# Connectors.net
KiCad netlist of a schematic drawn in Altium Designer
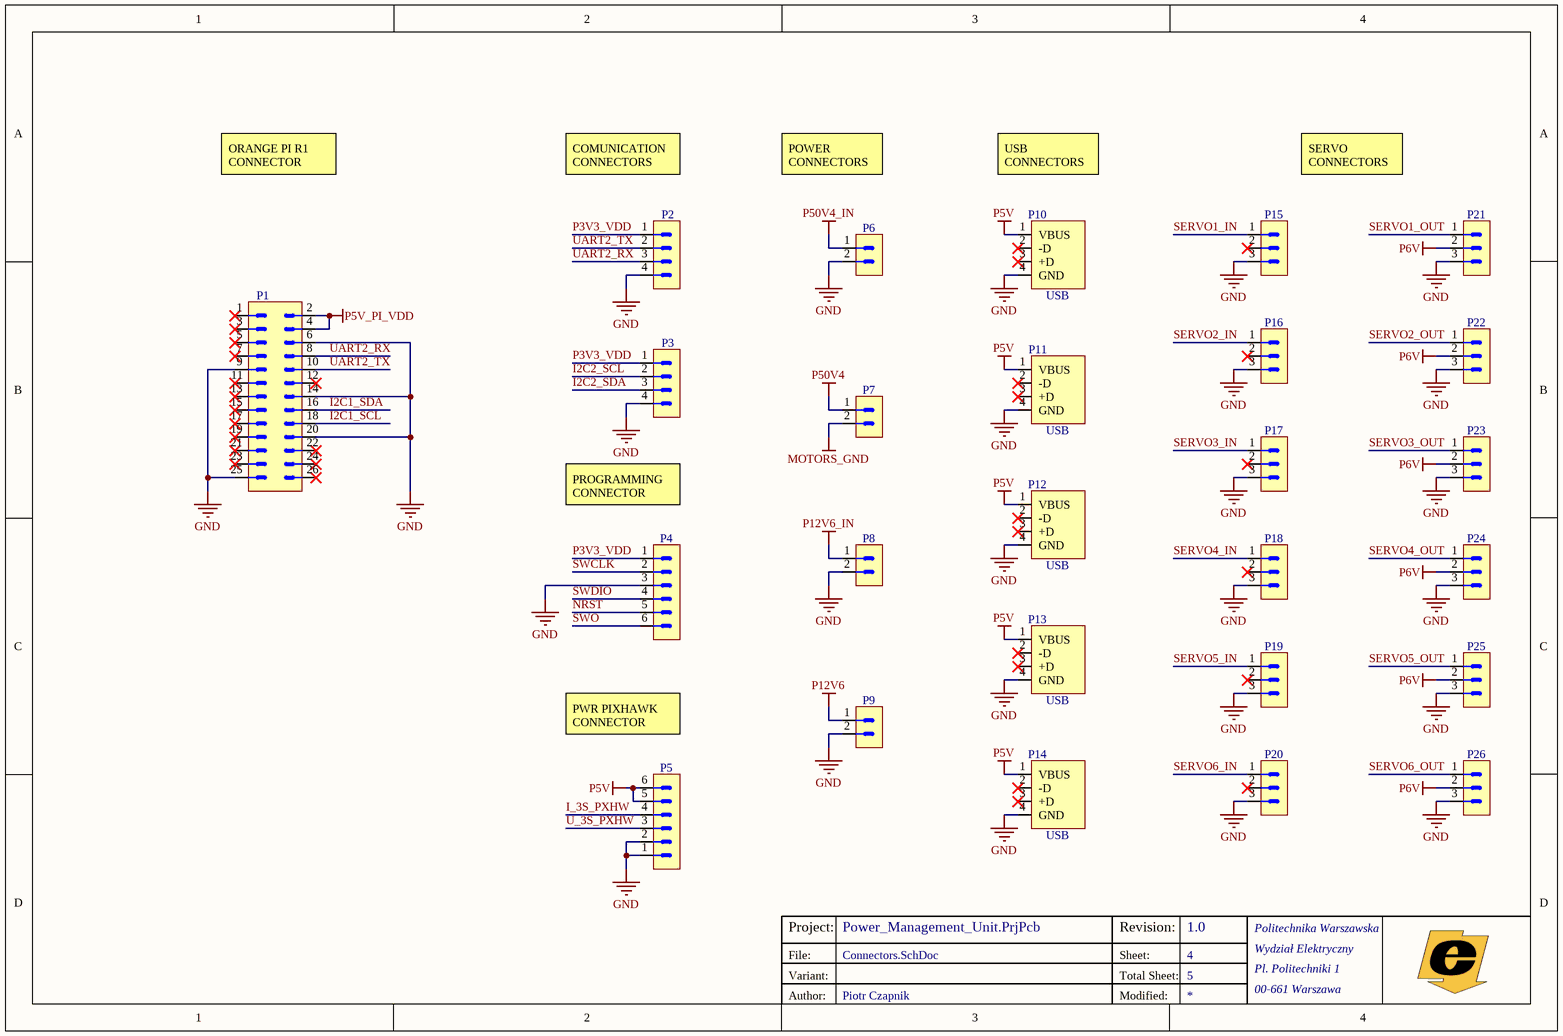
[diagram p0: Connectors.SchDoc]

(export (version "E")
  (design (tool "Eeschema 10.0.6"))
  (components
    (comp (ref "P1")
      (value "SAMTEC_SSW-113-02-G-D")
      (footprint "SAMTEC_SSW-113-02-G-D")
      (description "General Purpose Header: THT, 2.54mm, Female, Straight")
      (fields (field (name "MANUFACTURER") "GENERIC") (field (name "AUTHOR") "PC"))
      (libsource (lib "Connectors") (part "Header 13x2"))
    )
    (comp (ref "P2")
      (value "SAMTEC_TSW-104-07-G-S")
      (footprint "SAMTEC_TSW-104-07-G-S")
      (description "General Purpose Header: THT, 2.54mm, Male, Straight")
      (fields (field (name "MANUFACTURER") "GENERIC") (field (name "AUTHOR") "PC"))
      (libsource (lib "Connectors") (part "Header 4x1"))
    )
    (comp (ref "P3")
      (value "~")
      (footprint "BM04B-GHS-TBT")
      (description "JST GH series 4 pin vertical SMT connector, pitch 1.25mm, Right Angle")
      (fields
        (field (name "MANUFACTURER") "JST")
        (field (name "MANUFACTURER PART NUMBER") "BM04B-GHS-TBT (LF)(SN)")
        (field (name "AUTHOR") "PC")
      )
      (libsource (lib "Connectors") (part "Header 4x1"))
    )
    (comp (ref "P4")
      (value "MTLW-106-07-L-S-250")
      (footprint "SAMTEC_MTLW-106-07-L-S-250")
      (description "General Purpose Header: THT, 2.54mm, Male, Straight")
      (fields
        (field (name "MANUFACTURER") "GENERIC")
        (field (name "MANUFACTURER PART NUMBER") "HDR_THT_6X1V_M_2P54MM")
        (field (name "AUTHOR") "PC")
      )
      (libsource (lib "Connectors") (part "Header 6x1"))
    )
    (comp (ref "P5")
      (value "~")
      (footprint "BM06B-GHS-TBT")
      (description "JST GH series 6 pin vertical SMT connector, pitch 1.25mm, Right Angle")
      (fields
        (field (name "MANUFACTURER") "JST")
        (field (name "MANUFACTURER PART NUMBER") "BM06B-GHS-TBT (LF)(SN)")
        (field (name "AUTHOR") "PC")
      )
      (libsource (lib "") (part "Header 6x1_1"))
    )
    (comp (ref "P6")
      (value "XT60PW-M")
      (footprint "XT60PW-M")
      (description "XT60 male connector, right angle, 2 Positions, THT, 17.2x15.5mm body")
      (fields (field (name "MANUFACTURER") "GENERIC") (field (name "AUTHOR") "PC"))
      (libsource (lib "Connectors") (part "Header 2x1"))
    )
    (comp (ref "P7")
      (value "XT60PW-F")
      (footprint "XT60PW-F")
      (description "XT60 female connector, right angle, 2 Positions, THT, 17.2x15.5mm body")
      (fields (field (name "MANUFACTURER") "GENERIC") (field (name "AUTHOR") "PC"))
      (libsource (lib "Connectors") (part "Header 2x1"))
    )
    (comp (ref "P8")
      (value "XT60PW-M")
      (footprint "XT60PW-M")
      (description "XT60 male connector, right angle, 2 Positions, THT, 17.2x15.5mm body")
      (fields (field (name "MANUFACTURER") "GENERIC") (field (name "AUTHOR") "PC"))
      (libsource (lib "Connectors") (part "Header 2x1"))
    )
    (comp (ref "P9")
      (value "XT60PW-F")
      (footprint "XT60PW-F")
      (description "XT60 female connector, right angle, 2 Positions, THT, 17.2x15.5mm body")
      (fields (field (name "MANUFACTURER") "GENERIC") (field (name "AUTHOR") "PC"))
      (libsource (lib "Connectors") (part "Header 2x1"))
    )
    (comp (ref "P10")
      (value "USB")
      (footprint "USB-A-S-RA")
      (description "USB 2.0 Type A Female Connector 4-Pin THT")
      (fields
        (field (name "MANUFACTURER") "GENERIC")
        (field (name "MANUFACTURER PART NUMBER") "USB-A-S-RA")
        (field (name "AUTHOR") "BS")
      )
      (libsource (lib "Connectors") (part "Connector USB 4 Pin"))
    )
    (comp (ref "P11")
      (value "USB")
      (footprint "USB-A-S-RA")
      (description "USB 2.0 Type A Female Connector 4-Pin THT")
      (fields
        (field (name "MANUFACTURER") "GENERIC")
        (field (name "MANUFACTURER PART NUMBER") "USB-A-S-RA")
        (field (name "AUTHOR") "BS")
      )
      (libsource (lib "Connectors") (part "Connector USB 4 Pin"))
    )
    (comp (ref "P12")
      (value "USB")
      (footprint "USB-A-S-RA")
      (description "USB 2.0 Type A Female Connector 4-Pin THT")
      (fields
        (field (name "MANUFACTURER") "GENERIC")
        (field (name "MANUFACTURER PART NUMBER") "USB-A-S-RA")
        (field (name "AUTHOR") "BS")
      )
      (libsource (lib "Connectors") (part "Connector USB 4 Pin"))
    )
    (comp (ref "P13")
      (value "USB")
      (footprint "USB-A-S-RA")
      (description "USB 2.0 Type A Female Connector 4-Pin THT")
      (fields
        (field (name "MANUFACTURER") "GENERIC")
        (field (name "MANUFACTURER PART NUMBER") "USB-A-S-RA")
        (field (name "AUTHOR") "BS")
      )
      (libsource (lib "Connectors") (part "Connector USB 4 Pin"))
    )
    (comp (ref "P14")
      (value "USB")
      (footprint "USB-A-S-RA")
      (description "USB 2.0 Type A Female Connector 4-Pin THT")
      (fields
        (field (name "MANUFACTURER") "GENERIC")
        (field (name "MANUFACTURER PART NUMBER") "USB-A-S-RA")
        (field (name "AUTHOR") "BS")
      )
      (libsource (lib "Connectors") (part "Connector USB 4 Pin"))
    )
    (comp (ref "P15")
      (value "826926-3")
      (footprint "Header_3x1_2.54mm_M")
      (description "General Purpose Header: THT, 2.54mm, Male, Straight")
      (fields (field (name "MANUFACTURER") "GENERIC") (field (name "AUTHOR") "JK"))
      (libsource (lib "Connectors") (part "Header 3x1"))
    )
    (comp (ref "P16")
      (value "826926-3")
      (footprint "Header_3x1_2.54mm_M")
      (description "General Purpose Header: THT, 2.54mm, Male, Straight")
      (fields (field (name "MANUFACTURER") "GENERIC") (field (name "AUTHOR") "JK"))
      (libsource (lib "Connectors") (part "Header 3x1"))
    )
    (comp (ref "P17")
      (value "826926-3")
      (footprint "Header_3x1_2.54mm_M")
      (description "General Purpose Header: THT, 2.54mm, Male, Straight")
      (fields (field (name "MANUFACTURER") "GENERIC") (field (name "AUTHOR") "JK"))
      (libsource (lib "Connectors") (part "Header 3x1"))
    )
    (comp (ref "P18")
      (value "826926-3")
      (footprint "Header_3x1_2.54mm_M")
      (description "General Purpose Header: THT, 2.54mm, Male, Straight")
      (fields (field (name "MANUFACTURER") "GENERIC") (field (name "AUTHOR") "JK"))
      (libsource (lib "Connectors") (part "Header 3x1"))
    )
    (comp (ref "P19")
      (value "826926-3")
      (footprint "Header_3x1_2.54mm_M")
      (description "General Purpose Header: THT, 2.54mm, Male, Straight")
      (fields (field (name "MANUFACTURER") "GENERIC") (field (name "AUTHOR") "JK"))
      (libsource (lib "Connectors") (part "Header 3x1"))
    )
    (comp (ref "P20")
      (value "826926-3")
      (footprint "Header_3x1_2.54mm_M")
      (description "General Purpose Header: THT, 2.54mm, Male, Straight")
      (fields (field (name "MANUFACTURER") "GENERIC") (field (name "AUTHOR") "JK"))
      (libsource (lib "Connectors") (part "Header 3x1"))
    )
    (comp (ref "P21")
      (value "826926-3")
      (footprint "Header_3x1_2.54mm_M")
      (description "General Purpose Header: THT, 2.54mm, Male, Straight")
      (fields (field (name "MANUFACTURER") "GENERIC") (field (name "AUTHOR") "JK"))
      (libsource (lib "Connectors") (part "Header 3x1"))
    )
    (comp (ref "P22")
      (value "826926-3")
      (footprint "Header_3x1_2.54mm_M")
      (description "General Purpose Header: THT, 2.54mm, Male, Straight")
      (fields (field (name "MANUFACTURER") "GENERIC") (field (name "AUTHOR") "JK"))
      (libsource (lib "Connectors") (part "Header 3x1"))
    )
    (comp (ref "P23")
      (value "826926-3")
      (footprint "Header_3x1_2.54mm_M")
      (description "General Purpose Header: THT, 2.54mm, Male, Straight")
      (fields (field (name "MANUFACTURER") "GENERIC") (field (name "AUTHOR") "JK"))
      (libsource (lib "Connectors") (part "Header 3x1"))
    )
    (comp (ref "P24")
      (value "826926-3")
      (footprint "Header_3x1_2.54mm_M")
      (description "General Purpose Header: THT, 2.54mm, Male, Straight")
      (fields (field (name "MANUFACTURER") "GENERIC") (field (name "AUTHOR") "JK"))
      (libsource (lib "Connectors") (part "Header 3x1"))
    )
    (comp (ref "P25")
      (value "826926-3")
      (footprint "Header_3x1_2.54mm_M")
      (description "General Purpose Header: THT, 2.54mm, Male, Straight")
      (fields (field (name "MANUFACTURER") "GENERIC") (field (name "AUTHOR") "JK"))
      (libsource (lib "Connectors") (part "Header 3x1"))
    )
    (comp (ref "P26")
      (value "826926-3")
      (footprint "Header_3x1_2.54mm_M")
      (description "General Purpose Header: THT, 2.54mm, Male, Straight")
      (fields (field (name "MANUFACTURER") "GENERIC") (field (name "AUTHOR") "JK"))
      (libsource (lib "Connectors") (part "Header 3x1"))
    )
  )
  (nets
    (net (code "1") (name "/I2C1_SCL") (class "Default")
      (node (ref "P1") (pin "18") (pinfunction "18_18") (pintype "passive"))
    )
    (net (code "2") (name "/I2C1_SDA") (class "Default")
      (node (ref "P1") (pin "16") (pinfunction "16_16") (pintype "passive"))
    )
    (net (code "3") (name "/I2C2_SCL") (class "Default")
      (node (ref "P3") (pin "2") (pinfunction "2_2") (pintype "passive"))
    )
    (net (code "4") (name "/I2C2_SDA") (class "Default")
      (node (ref "P3") (pin "3") (pinfunction "3_3") (pintype "passive"))
    )
    (net (code "5") (name "/I_3S_PXHW") (class "Default")
      (node (ref "P5") (pin "4") (pinfunction "4_4") (pintype "passive"))
    )
    (net (code "6") (name "/NRST") (class "Default")
      (node (ref "P4") (pin "5") (pinfunction "5_5") (pintype "passive"))
    )
    (net (code "7") (name "/P3V3_VDD") (class "Default")
      (node (ref "P2") (pin "1") (pinfunction "1_1") (pintype "passive"))
      (node (ref "P3") (pin "1") (pinfunction "1_1") (pintype "passive"))
      (node (ref "P4") (pin "1") (pinfunction "1_1") (pintype "passive"))
    )
    (net (code "8") (name "/SERVO1_IN") (class "Default")
      (node (ref "P15") (pin "1") (pinfunction "1_1") (pintype "passive"))
    )
    (net (code "9") (name "/SERVO1_OUT") (class "Default")
      (node (ref "P21") (pin "1") (pinfunction "1_1") (pintype "passive"))
    )
    (net (code "10") (name "/SERVO2_IN") (class "Default")
      (node (ref "P16") (pin "1") (pinfunction "1_1") (pintype "passive"))
    )
    (net (code "11") (name "/SERVO2_OUT") (class "Default")
      (node (ref "P22") (pin "1") (pinfunction "1_1") (pintype "passive"))
    )
    (net (code "12") (name "/SERVO3_IN") (class "Default")
      (node (ref "P17") (pin "1") (pinfunction "1_1") (pintype "passive"))
    )
    (net (code "13") (name "/SERVO3_OUT") (class "Default")
      (node (ref "P23") (pin "1") (pinfunction "1_1") (pintype "passive"))
    )
    (net (code "14") (name "/SERVO4_IN") (class "Default")
      (node (ref "P18") (pin "1") (pinfunction "1_1") (pintype "passive"))
    )
    (net (code "15") (name "/SERVO4_OUT") (class "Default")
      (node (ref "P24") (pin "1") (pinfunction "1_1") (pintype "passive"))
    )
    (net (code "16") (name "/SERVO5_IN") (class "Default")
      (node (ref "P19") (pin "1") (pinfunction "1_1") (pintype "passive"))
    )
    (net (code "17") (name "/SERVO5_OUT") (class "Default")
      (node (ref "P25") (pin "1") (pinfunction "1_1") (pintype "passive"))
    )
    (net (code "18") (name "/SERVO6_IN") (class "Default")
      (node (ref "P20") (pin "1") (pinfunction "1_1") (pintype "passive"))
    )
    (net (code "19") (name "/SERVO6_OUT") (class "Default")
      (node (ref "P26") (pin "1") (pinfunction "1_1") (pintype "passive"))
    )
    (net (code "20") (name "/SWCLK") (class "Default")
      (node (ref "P4") (pin "2") (pinfunction "2_2") (pintype "passive"))
    )
    (net (code "21") (name "/SWDIO") (class "Default")
      (node (ref "P4") (pin "4") (pinfunction "4_4") (pintype "passive"))
    )
    (net (code "22") (name "/SWO") (class "Default")
      (node (ref "P4") (pin "6") (pinfunction "6_6") (pintype "passive"))
    )
    (net (code "23") (name "/UART2_RX") (class "Default")
      (node (ref "P1") (pin "8") (pinfunction "8_8") (pintype "passive"))
      (node (ref "P2") (pin "3") (pinfunction "3_3") (pintype "passive"))
    )
    (net (code "24") (name "/UART2_TX") (class "Default")
      (node (ref "P1") (pin "10") (pinfunction "10_10") (pintype "passive"))
      (node (ref "P2") (pin "2") (pinfunction "2_2") (pintype "passive"))
    )
    (net (code "25") (name "/U_3S_PXHW") (class "Default")
      (node (ref "P5") (pin "3") (pinfunction "3_3") (pintype "passive"))
    )
    (net (code "26") (name "GND") (class "Default")
      (node (ref "P1") (pin "14") (pinfunction "14_14") (pintype "passive"))
      (node (ref "P1") (pin "20") (pinfunction "20_20") (pintype "passive"))
      (node (ref "P1") (pin "25") (pinfunction "25_25") (pintype "passive"))
      (node (ref "P1") (pin "6") (pinfunction "6_6") (pintype "passive"))
      (node (ref "P1") (pin "9") (pinfunction "9_9") (pintype "passive"))
      (node (ref "P10") (pin "4") (pinfunction "GND_4") (pintype "passive"))
      (node (ref "P11") (pin "4") (pinfunction "GND_4") (pintype "passive"))
      (node (ref "P12") (pin "4") (pinfunction "GND_4") (pintype "passive"))
      (node (ref "P13") (pin "4") (pinfunction "GND_4") (pintype "passive"))
      (node (ref "P14") (pin "4") (pinfunction "GND_4") (pintype "passive"))
      (node (ref "P15") (pin "3") (pinfunction "3_3") (pintype "passive"))
      (node (ref "P16") (pin "3") (pinfunction "3_3") (pintype "passive"))
      (node (ref "P17") (pin "3") (pinfunction "3_3") (pintype "passive"))
      (node (ref "P18") (pin "3") (pinfunction "3_3") (pintype "passive"))
      (node (ref "P19") (pin "3") (pinfunction "3_3") (pintype "passive"))
      (node (ref "P2") (pin "4") (pinfunction "4_4") (pintype "passive"))
      (node (ref "P20") (pin "3") (pinfunction "3_3") (pintype "passive"))
      (node (ref "P21") (pin "3") (pinfunction "3_3") (pintype "passive"))
      (node (ref "P22") (pin "3") (pinfunction "3_3") (pintype "passive"))
      (node (ref "P23") (pin "3") (pinfunction "3_3") (pintype "passive"))
      (node (ref "P24") (pin "3") (pinfunction "3_3") (pintype "passive"))
      (node (ref "P25") (pin "3") (pinfunction "3_3") (pintype "passive"))
      (node (ref "P26") (pin "3") (pinfunction "3_3") (pintype "passive"))
      (node (ref "P3") (pin "4") (pinfunction "4_4") (pintype "passive"))
      (node (ref "P4") (pin "3") (pinfunction "3_3") (pintype "passive"))
      (node (ref "P5") (pin "1") (pinfunction "1_1") (pintype "passive"))
      (node (ref "P5") (pin "2") (pinfunction "2_2") (pintype "passive"))
      (node (ref "P6") (pin "2") (pinfunction "2_2") (pintype "passive"))
      (node (ref "P8") (pin "2") (pinfunction "2_2") (pintype "passive"))
      (node (ref "P9") (pin "2") (pinfunction "2_2") (pintype "passive"))
    )
    (net (code "27") (name "MOTORS_GND") (class "Default")
      (node (ref "P7") (pin "2") (pinfunction "2_2") (pintype "passive"))
    )
    (net (code "28") (name "P5V") (class "Default")
      (node (ref "P10") (pin "1") (pinfunction "VBUS_1") (pintype "passive"))
      (node (ref "P11") (pin "1") (pinfunction "VBUS_1") (pintype "passive"))
      (node (ref "P12") (pin "1") (pinfunction "VBUS_1") (pintype "passive"))
      (node (ref "P13") (pin "1") (pinfunction "VBUS_1") (pintype "passive"))
      (node (ref "P14") (pin "1") (pinfunction "VBUS_1") (pintype "passive"))
      (node (ref "P5") (pin "5") (pinfunction "5_5") (pintype "passive"))
      (node (ref "P5") (pin "6") (pinfunction "6_6") (pintype "passive"))
    )
    (net (code "29") (name "P5V_PI_VDD") (class "Default")
      (node (ref "P1") (pin "2") (pinfunction "2_2") (pintype "passive"))
      (node (ref "P1") (pin "4") (pinfunction "4_4") (pintype "passive"))
    )
    (net (code "30") (name "P6V") (class "Default")
      (node (ref "P21") (pin "2") (pinfunction "2_2") (pintype "passive"))
      (node (ref "P22") (pin "2") (pinfunction "2_2") (pintype "passive"))
      (node (ref "P23") (pin "2") (pinfunction "2_2") (pintype "passive"))
      (node (ref "P24") (pin "2") (pinfunction "2_2") (pintype "passive"))
      (node (ref "P25") (pin "2") (pinfunction "2_2") (pintype "passive"))
      (node (ref "P26") (pin "2") (pinfunction "2_2") (pintype "passive"))
    )
    (net (code "31") (name "P12V6") (class "Default")
      (node (ref "P9") (pin "1") (pinfunction "1_1") (pintype "passive"))
    )
    (net (code "32") (name "P12V6_IN") (class "Default")
      (node (ref "P8") (pin "1") (pinfunction "1_1") (pintype "passive"))
    )
    (net (code "33") (name "P50V4") (class "Default")
      (node (ref "P7") (pin "1") (pinfunction "1_1") (pintype "passive"))
    )
    (net (code "34") (name "P50V4_IN") (class "Default")
      (node (ref "P6") (pin "1") (pinfunction "1_1") (pintype "passive"))
    )
    (net (code "35") (name "unconnected-(P1-12-Pad11)") (class "Default")
      (node (ref "P1") (pin "11") (pinfunction "12_11") (pintype "passive+no_connect"))
    )
    (net (code "36") (name "unconnected-(P1-Pad1)") (class "Default")
      (node (ref "P1") (pin "1") (pinfunction "1_1") (pintype "passive+no_connect"))
    )
    (net (code "37") (name "unconnected-(P1-Pad3)") (class "Default")
      (node (ref "P1") (pin "3") (pinfunction "3_3") (pintype "passive+no_connect"))
    )
    (net (code "38") (name "unconnected-(P1-Pad5)") (class "Default")
      (node (ref "P1") (pin "5") (pinfunction "5_5") (pintype "passive+no_connect"))
    )
    (net (code "39") (name "unconnected-(P1-Pad7)") (class "Default")
      (node (ref "P1") (pin "7") (pinfunction "7_7") (pintype "passive+no_connect"))
    )
    (net (code "40") (name "unconnected-(P1-Pad12)") (class "Default")
      (node (ref "P1") (pin "12") (pinfunction "12_12") (pintype "passive+no_connect"))
    )
    (net (code "41") (name "unconnected-(P1-Pad13)") (class "Default")
      (node (ref "P1") (pin "13") (pinfunction "13_13") (pintype "passive+no_connect"))
    )
    (net (code "42") (name "unconnected-(P1-Pad15)") (class "Default")
      (node (ref "P1") (pin "15") (pinfunction "15_15") (pintype "passive+no_connect"))
    )
    (net (code "43") (name "unconnected-(P1-Pad17)") (class "Default")
      (node (ref "P1") (pin "17") (pinfunction "17_17") (pintype "passive+no_connect"))
    )
    (net (code "44") (name "unconnected-(P1-Pad19)") (class "Default")
      (node (ref "P1") (pin "19") (pinfunction "19_19") (pintype "passive+no_connect"))
    )
    (net (code "45") (name "unconnected-(P1-Pad21)") (class "Default")
      (node (ref "P1") (pin "21") (pinfunction "21_21") (pintype "passive+no_connect"))
    )
    (net (code "46") (name "unconnected-(P1-Pad22)") (class "Default")
      (node (ref "P1") (pin "22") (pinfunction "22_22") (pintype "passive+no_connect"))
    )
    (net (code "47") (name "unconnected-(P1-Pad23)") (class "Default")
      (node (ref "P1") (pin "23") (pinfunction "23_23") (pintype "passive+no_connect"))
    )
    (net (code "48") (name "unconnected-(P1-Pad24)") (class "Default")
      (node (ref "P1") (pin "24") (pinfunction "24_24") (pintype "passive+no_connect"))
    )
    (net (code "49") (name "unconnected-(P1-Pad26)") (class "Default")
      (node (ref "P1") (pin "26") (pinfunction "26_26") (pintype "passive+no_connect"))
    )
    (net (code "50") (name "unconnected-(P10-+D-Pad3)") (class "Default")
      (node (ref "P10") (pin "3") (pinfunction "+D_3") (pintype "passive+no_connect"))
    )
    (net (code "51") (name "unconnected-(P10--D-Pad2)") (class "Default")
      (node (ref "P10") (pin "2") (pinfunction "-D_2") (pintype "passive+no_connect"))
    )
    (net (code "52") (name "unconnected-(P11-+D-Pad3)") (class "Default")
      (node (ref "P11") (pin "3") (pinfunction "+D_3") (pintype "passive+no_connect"))
    )
    (net (code "53") (name "unconnected-(P11--D-Pad2)") (class "Default")
      (node (ref "P11") (pin "2") (pinfunction "-D_2") (pintype "passive+no_connect"))
    )
    (net (code "54") (name "unconnected-(P12-+D-Pad3)") (class "Default")
      (node (ref "P12") (pin "3") (pinfunction "+D_3") (pintype "passive+no_connect"))
    )
    (net (code "55") (name "unconnected-(P12--D-Pad2)") (class "Default")
      (node (ref "P12") (pin "2") (pinfunction "-D_2") (pintype "passive+no_connect"))
    )
    (net (code "56") (name "unconnected-(P13-+D-Pad3)") (class "Default")
      (node (ref "P13") (pin "3") (pinfunction "+D_3") (pintype "passive+no_connect"))
    )
    (net (code "57") (name "unconnected-(P13--D-Pad2)") (class "Default")
      (node (ref "P13") (pin "2") (pinfunction "-D_2") (pintype "passive+no_connect"))
    )
    (net (code "58") (name "unconnected-(P14-+D-Pad3)") (class "Default")
      (node (ref "P14") (pin "3") (pinfunction "+D_3") (pintype "passive+no_connect"))
    )
    (net (code "59") (name "unconnected-(P14--D-Pad2)") (class "Default")
      (node (ref "P14") (pin "2") (pinfunction "-D_2") (pintype "passive+no_connect"))
    )
    (net (code "60") (name "unconnected-(P15-Pad2)") (class "Default")
      (node (ref "P15") (pin "2") (pinfunction "2_2") (pintype "passive+no_connect"))
    )
    (net (code "61") (name "unconnected-(P16-Pad2)") (class "Default")
      (node (ref "P16") (pin "2") (pinfunction "2_2") (pintype "passive+no_connect"))
    )
    (net (code "62") (name "unconnected-(P17-Pad2)") (class "Default")
      (node (ref "P17") (pin "2") (pinfunction "2_2") (pintype "passive+no_connect"))
    )
    (net (code "63") (name "unconnected-(P18-Pad2)") (class "Default")
      (node (ref "P18") (pin "2") (pinfunction "2_2") (pintype "passive+no_connect"))
    )
    (net (code "64") (name "unconnected-(P19-Pad2)") (class "Default")
      (node (ref "P19") (pin "2") (pinfunction "2_2") (pintype "passive+no_connect"))
    )
    (net (code "65") (name "unconnected-(P20-Pad2)") (class "Default")
      (node (ref "P20") (pin "2") (pinfunction "2_2") (pintype "passive+no_connect"))
    )
  )
)
